# Switches.net
KiCad netlist of a schematic drawn in Altium Designer
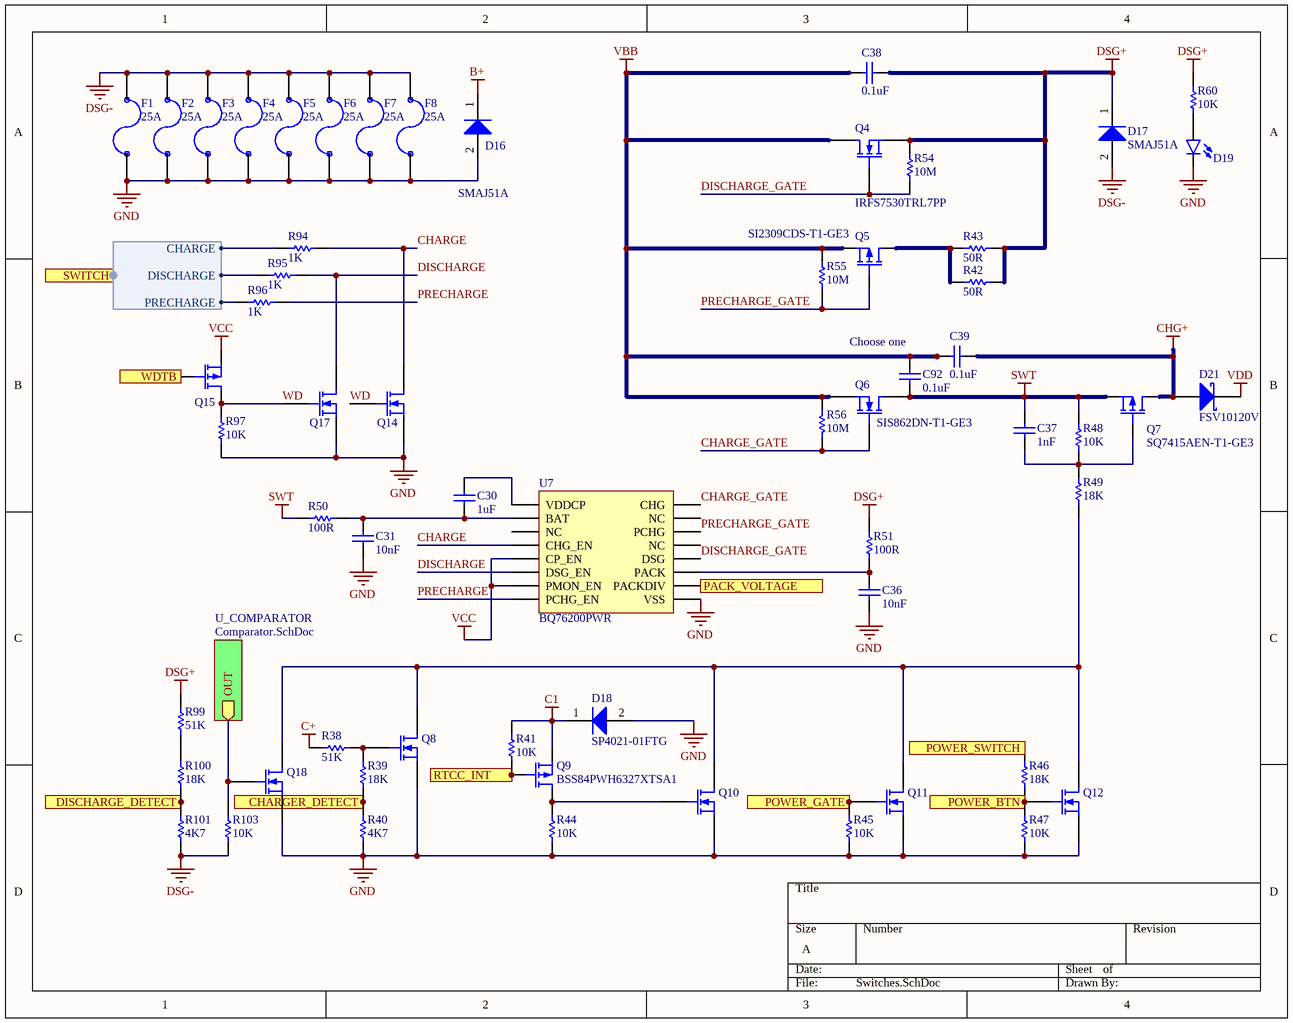
[diagram p0: Switches.SchDoc]

(export (version "E")
  (design (tool "Eeschema 10.0.6"))
  (components
    (comp (ref "C30")
      (value "1uF")
      (footprint "C0603[1608X92]")
      (description "1uF 50V 10% 0603 (1608 Metric)")
      (fields (field (name "TOLERANCE") "10%") (field (name "PARTNUMBER") "GRM188R61H105KAALD"))
      (libsource (lib "Capacitors") (part "CAP_1uF_50V_0603_10%"))
    )
    (comp (ref "C31")
      (value "10nF")
      (footprint "C0603[1608X92]")
      (description "10nF 100V 10% 0603 (1608 Metric)")
      (fields (field (name "TOLERANCE") "10%") (field (name "PARTNUMBER") "GRM188R72A103KA01D"))
      (libsource (lib "Capacitors") (part "CAP_10nF_100V_0603_10%"))
    )
    (comp (ref "C36")
      (value "10nF")
      (footprint "C0603[1608X92]")
      (description "10nF 100V 10% 0603 (1608 Metric)")
      (fields (field (name "TOLERANCE") "10%") (field (name "PARTNUMBER") "GRM188R72A103KA01D"))
      (libsource (lib "Capacitors") (part "CAP_10nF_100V_0603_10%"))
    )
    (comp (ref "C37")
      (value "1nF")
      (footprint "C0603[1608X92]")
      (description "1nF 50V 5% 0603 (1608 Metric)")
      (fields (field (name "PARTNUMBER") "GRM1885C1H102JA01D") (field (name "MANUFACTURER") "Murata"))
      (libsource (lib "Capacitors") (part "CAP_1nF_50V_0603_5%"))
    )
    (comp (ref "C38")
      (value "0.1uF")
      (footprint "C0603[1608X92]")
      (description "0.1uF 100V 10% 0603 (1608 Metric)")
      (fields (field (name "PARTNUMBER") "GRM188R72A104KA35D") (field (name "MANUFACTURER") "Murata"))
      (libsource (lib "Capacitors") (part "CAP_0.1uF_100V_0603_10%"))
    )
    (comp (ref "C39")
      (value "0.1uF")
      (footprint "C0603[1608X92]")
      (description "0.1uF 100V 10% 0603 (1608 Metric)")
      (fields (field (name "PARTNUMBER") "GRM188R72A104KA35D") (field (name "MANUFACTURER") "Murata"))
      (libsource (lib "Capacitors") (part "CAP_0.1uF_100V_0603_10%"))
    )
    (comp (ref "C92")
      (value "0.1uF")
      (footprint "C0603[1608X92]")
      (description "0.1uF 100V 10% 0603 (1608 Metric)")
      (fields (field (name "PARTNUMBER") "GRM188R72A104KA35D") (field (name "MANUFACTURER") "Murata"))
      (libsource (lib "Capacitors") (part "CAP_0.1uF_100V_0603_10%"))
    )
    (comp (ref "D16")
      (value "SMAJ51A")
      (footprint "DO-214AC")
      (fields (field (name "PARTNUMBER") "SMAJ51A-E3/61") (field (name "MANUFACTURER") "Vishay"))
      (libsource (lib "Diodes") (part "SMAJ51A-E3/61"))
    )
    (comp (ref "D17")
      (value "SMAJ51A")
      (footprint "DO-214AC")
      (fields (field (name "PARTNUMBER") "SMAJ51A-E3/61") (field (name "MANUFACTURER") "Vishay"))
      (libsource (lib "Diodes") (part "SMAJ51A-E3/61"))
    )
    (comp (ref "D18")
      (value "SP4021-01FTG")
      (footprint "SOD-323")
      (fields (field (name "MANUFACTURER") "Littelfuse"))
      (libsource (lib "Diodes") (part "SP4021-01FTG"))
    )
    (comp (ref "D19")
      (value "LED_0603_GREEN_5mA")
      (footprint "LED0603")
      (fields (field (name "PARTNUMBER") "LTST-C193TGKT-5A") (field (name "MANUFACTURER") "Lite-On Inc."))
      (libsource (lib "LEDs") (part "LED_0603_GREEN_5mA"))
    )
    (comp (ref "D21")
      (value "FSV10120V")
      (footprint "TO-277")
      (description "Schottky Diodes & Rectifiers 10 Amp 120V Schottky Rectifier")
      (fields (field (name "MANUFACTURER") "Fairchild Semiconductor"))
      (libsource (lib "Diodes") (part "FSV10120V"))
    )
    (comp (ref "F1")
      (value "FUSE 1206")
      (footprint "1206_FUSE")
      (description "Surface Mount Fuses UST 1206 FUSE 25A F")
      (fields
        (field (name "PARTNUMBER") "3413.0332.22")
        (field (name "MANUFACTURER") "Schurter")
        (field (name "CURRENT") "25A")
      )
      (libsource (lib "Components") (part "FUSE 1206"))
    )
    (comp (ref "F2")
      (value "FUSE 1206")
      (footprint "1206_FUSE")
      (description "Surface Mount Fuses UST 1206 FUSE 25A F")
      (fields
        (field (name "PARTNUMBER") "3413.0332.22")
        (field (name "MANUFACTURER") "Schurter")
        (field (name "CURRENT") "25A")
      )
      (libsource (lib "Components") (part "FUSE 1206"))
    )
    (comp (ref "F3")
      (value "FUSE 1206")
      (footprint "1206_FUSE")
      (description "Surface Mount Fuses UST 1206 FUSE 25A F")
      (fields
        (field (name "PARTNUMBER") "3413.0332.22")
        (field (name "MANUFACTURER") "Schurter")
        (field (name "CURRENT") "25A")
      )
      (libsource (lib "Components") (part "FUSE 1206"))
    )
    (comp (ref "F4")
      (value "FUSE 1206")
      (footprint "1206_FUSE")
      (description "Surface Mount Fuses UST 1206 FUSE 25A F")
      (fields
        (field (name "PARTNUMBER") "3413.0332.22")
        (field (name "MANUFACTURER") "Schurter")
        (field (name "CURRENT") "25A")
      )
      (libsource (lib "Components") (part "FUSE 1206"))
    )
    (comp (ref "F5")
      (value "FUSE 1206")
      (footprint "1206_FUSE")
      (description "Surface Mount Fuses UST 1206 FUSE 25A F")
      (fields
        (field (name "PARTNUMBER") "3413.0332.22")
        (field (name "MANUFACTURER") "Schurter")
        (field (name "CURRENT") "25A")
      )
      (libsource (lib "Components") (part "FUSE 1206"))
    )
    (comp (ref "F6")
      (value "FUSE 1206")
      (footprint "1206_FUSE")
      (description "Surface Mount Fuses UST 1206 FUSE 25A F")
      (fields
        (field (name "PARTNUMBER") "3413.0332.22")
        (field (name "MANUFACTURER") "Schurter")
        (field (name "CURRENT") "25A")
      )
      (libsource (lib "Components") (part "FUSE 1206"))
    )
    (comp (ref "F7")
      (value "FUSE 1206")
      (footprint "1206_FUSE")
      (description "Surface Mount Fuses UST 1206 FUSE 25A F")
      (fields
        (field (name "PARTNUMBER") "3413.0332.22")
        (field (name "MANUFACTURER") "Schurter")
        (field (name "CURRENT") "25A")
      )
      (libsource (lib "Components") (part "FUSE 1206"))
    )
    (comp (ref "F8")
      (value "FUSE 1206")
      (footprint "1206_FUSE")
      (description "Surface Mount Fuses UST 1206 FUSE 25A F")
      (fields
        (field (name "PARTNUMBER") "3413.0332.22")
        (field (name "MANUFACTURER") "Schurter")
        (field (name "CURRENT") "25A")
      )
      (libsource (lib "Components") (part "FUSE 1206"))
    )
    (comp (ref "Q4")
      (value "IRFS7530TRL7PP")
      (footprint "D2PAK-7  w/Heatsink")
      (description "N-Channel MOSFET")
      (fields (field (name "MANUFACTURER") "Infineon") (field (name "PUBLISHER") "Altium Limited"))
      (libsource (lib "MOSFETs") (part "IRFS7530TRL7PP"))
    )
    (comp (ref "Q5")
      (value "SI2309CDS-T1-GE3")
      (footprint "SOT23-3")
      (description "P-Channel MOSFET")
      (fields (field (name "MANUFACTURER") "Vishay"))
      (libsource (lib "MOSFETs") (part "SI2309CDS-T1-GE3"))
    )
    (comp (ref "Q6")
      (value "SIS862DN-T1-GE3")
      (footprint "PowerPak-1212-8")
      (description "N-Channel MOSFET")
      (fields (field (name "MANUFACTURER") "Vishay"))
      (libsource (lib "MOSFETs") (part "SIS862DN-T1-GE3"))
    )
    (comp (ref "Q7")
      (value "SQ7415AEN-T1-GE3")
      (footprint "PowerPak-1212-8")
      (description "P-Channel MOSFET")
      (fields (field (name "MANUFACTURER") "Vishay"))
      (libsource (lib "MOSFETs") (part "SQ7415AEN-T1-GE3"))
    )
    (comp (ref "Q8")
      (value "BSS123WQ-7-F")
      (footprint "SOT323-3")
      (description "N-Channel MOSFET")
      (fields (field (name "MANUFACTURER") "Diodes Incorporated"))
      (libsource (lib "MOSFETs") (part "BSS123WQ-7-F"))
    )
    (comp (ref "Q9")
      (value "BSS84PWH6327XTSA1")
      (footprint "SOT323-3")
      (description "P-Channel MOSFET")
      (fields (field (name "MANUFACTURER") "Infineon"))
      (libsource (lib "MOSFETs") (part "BSS84PW H6327"))
    )
    (comp (ref "Q10")
      (value "BSS123WQ-7-F")
      (footprint "SOT323-3")
      (description "N-Channel MOSFET")
      (fields (field (name "MANUFACTURER") "Diodes Incorporated"))
      (libsource (lib "MOSFETs") (part "BSS123WQ-7-F"))
    )
    (comp (ref "Q11")
      (value "BSS123WQ-7-F")
      (footprint "SOT323-3")
      (description "N-Channel MOSFET")
      (fields (field (name "MANUFACTURER") "Diodes Incorporated"))
      (libsource (lib "MOSFETs") (part "BSS123WQ-7-F"))
    )
    (comp (ref "Q12")
      (value "BSS123WQ-7-F")
      (footprint "SOT323-3")
      (description "N-Channel MOSFET")
      (fields (field (name "MANUFACTURER") "Diodes Incorporated"))
      (libsource (lib "MOSFETs") (part "BSS123WQ-7-F"))
    )
    (comp (ref "Q14")
      (value "BSS123WQ-7-F")
      (footprint "SOT323-3")
      (description "N-Channel MOSFET")
      (fields (field (name "MANUFACTURER") "Diodes Incorporated"))
      (libsource (lib "MOSFETs") (part "BSS123WQ-7-F"))
    )
    (comp (ref "Q15")
      (value "BSS84PWH6327XTSA1")
      (footprint "SOT323-3")
      (description "P-Channel MOSFET")
      (fields (field (name "MANUFACTURER") "Infineon"))
      (libsource (lib "MOSFETs") (part "BSS84PW H6327"))
    )
    (comp (ref "Q17")
      (value "BSS123WQ-7-F")
      (footprint "SOT323-3")
      (description "N-Channel MOSFET")
      (fields (field (name "MANUFACTURER") "Diodes Incorporated"))
      (libsource (lib "MOSFETs") (part "BSS123WQ-7-F"))
    )
    (comp (ref "Q18")
      (value "BSS123WQ-7-F")
      (footprint "SOT323-3")
      (description "N-Channel MOSFET")
      (fields (field (name "MANUFACTURER") "Diodes Incorporated"))
      (libsource (lib "MOSFETs") (part "BSS123WQ-7-F"))
    )
    (comp (ref "R38")
      (value "51K")
      (footprint "R0603[1608]")
      (description "51K 0.25W 1% 0603 (1005 Metric)")
      (fields (field (name "POWER") "0.25W") (field (name "TOLERANCE") "1%"))
      (libsource (lib "Resistors") (part "RES_51K_0603_1%"))
    )
    (comp (ref "R39")
      (value "18K")
      (footprint "R0603[1608]")
      (description "18K 0.25W 1% 0603 (1005 Metric)")
      (fields (field (name "TOLERANCE") "1%") (field (name "POWER") "0.25W"))
      (libsource (lib "Resistors") (part "RES_18K_0603_1%"))
    )
    (comp (ref "R40")
      (value "4K7")
      (footprint "R0603[1608]")
      (description "4K7 0.25W 1% 0603 (1005 Metric)")
      (fields (field (name "TOLERANCE") "1%") (field (name "POWER") "0.25W"))
      (libsource (lib "Resistors") (part "RES_4K7_0603_1%"))
    )
    (comp (ref "R41")
      (value "10K")
      (footprint "R0603[1608]")
      (description "10K 0.25W 1% 0603 (1005 Metric)")
      (fields (field (name "MANUFACTURER") "Vishay / Dale") (field (name "PARTNUMBER") "CRCW060310K0FKEAHP"))
      (libsource (lib "Resistors") (part "RES_10K_0603_1%"))
    )
    (comp (ref "R42")
      (value "50R")
      (footprint "R1206[3216]")
      (description "50R 2.4W 2% 1206 (3216 Metric)")
      (fields (field (name "TOLERANCE") "2%") (field (name "POWER") "2.4W"))
      (libsource (lib "Resistors") (part "RES_50R_1206_2%"))
    )
    (comp (ref "R43")
      (value "50R")
      (footprint "R1206[3216]")
      (description "50R 2.4W 2% 1206 (3216 Metric)")
      (fields (field (name "TOLERANCE") "2%") (field (name "POWER") "2.4W"))
      (libsource (lib "Resistors") (part "RES_50R_1206_2%"))
    )
    (comp (ref "R44")
      (value "10K")
      (footprint "R0603[1608]")
      (description "10K 0.25W 1% 0603 (1005 Metric)")
      (fields (field (name "MANUFACTURER") "Vishay / Dale") (field (name "PARTNUMBER") "CRCW060310K0FKEAHP"))
      (libsource (lib "Resistors") (part "RES_10K_0603_1%"))
    )
    (comp (ref "R45")
      (value "10K")
      (footprint "R0603[1608]")
      (description "10K 0.25W 1% 0603 (1005 Metric)")
      (fields (field (name "MANUFACTURER") "Vishay / Dale") (field (name "PARTNUMBER") "CRCW060310K0FKEAHP"))
      (libsource (lib "Resistors") (part "RES_10K_0603_1%"))
    )
    (comp (ref "R46")
      (value "18K")
      (footprint "R0603[1608]")
      (description "18K 0.25W 1% 0603 (1005 Metric)")
      (fields (field (name "TOLERANCE") "1%") (field (name "POWER") "0.25W"))
      (libsource (lib "Resistors") (part "RES_18K_0603_1%"))
    )
    (comp (ref "R47")
      (value "10K")
      (footprint "R0603[1608]")
      (description "10K 0.25W 1% 0603 (1005 Metric)")
      (fields (field (name "POWER") "0.25W") (field (name "TOLERANCE") "1%"))
      (libsource (lib "Resistors") (part "RES_10K_0603_1%"))
    )
    (comp (ref "R48")
      (value "10K")
      (footprint "R0603[1608]")
      (description "10K 0.25W 1% 0603 (1005 Metric)")
      (fields (field (name "TOLERANCE") "1%") (field (name "POWER") "0.25W"))
      (libsource (lib "Resistors") (part "RES_10K_0603_1%"))
    )
    (comp (ref "R49")
      (value "18K")
      (footprint "R0603[1608]")
      (description "18K 0.25W 1% 0603 (1005 Metric)")
      (fields (field (name "POWER") "0.25W") (field (name "TOLERANCE") "1%"))
      (libsource (lib "Resistors") (part "RES_18K_0603_1%"))
    )
    (comp (ref "R50")
      (value "100R")
      (footprint "R0603[1608]")
      (description "100R 0.25W 1% 0603 (1005 Metric)")
      (fields (field (name "POWER") "0.25W") (field (name "TOLERANCE") "1%"))
      (libsource (lib "Resistors") (part "RES_100R_0603_1%"))
    )
    (comp (ref "R51")
      (value "100R")
      (footprint "R0603[1608]")
      (description "100R 0.25W 1% 0603 (1005 Metric)")
      (fields (field (name "POWER") "0.25W") (field (name "TOLERANCE") "1%"))
      (libsource (lib "Resistors") (part "RES_100R_0603_1%"))
    )
    (comp (ref "R54")
      (value "10M")
      (footprint "R0603[1608]")
      (description "10M 0.25W 1% 0603 (1005 Metric)")
      (fields (field (name "MANUFACTURER") "Vishay / Dale") (field (name "PARTNUMBER") "RCS060310M0FKEA"))
      (libsource (lib "Resistors") (part "RES_10M_0603_1%"))
    )
    (comp (ref "R55")
      (value "10M")
      (footprint "R0603[1608]")
      (description "10M 0.25W 1% 0603 (1005 Metric)")
      (fields (field (name "MANUFACTURER") "Vishay / Dale") (field (name "PARTNUMBER") "RCS060310M0FKEA"))
      (libsource (lib "Resistors") (part "RES_10M_0603_1%"))
    )
    (comp (ref "R56")
      (value "10M")
      (footprint "R0603[1608]")
      (description "10M 0.25W 1% 0603 (1005 Metric)")
      (fields (field (name "MANUFACTURER") "Vishay / Dale") (field (name "PARTNUMBER") "RCS060310M0FKEA"))
      (libsource (lib "Resistors") (part "RES_10M_0603_1%"))
    )
    (comp (ref "R60")
      (value "10K")
      (footprint "R0603[1608]")
      (description "10K 0.25W 1% 0603 (1005 Metric)")
      (fields (field (name "TOLERANCE") "1%") (field (name "POWER") "0.25W"))
      (libsource (lib "Resistors") (part "RES_10K_0603_1%"))
    )
    (comp (ref "R94")
      (value "1K")
      (footprint "R0603[1608]")
      (description "1K 0.25W 1% 0603 (1005 Metric)")
      (fields (field (name "MANUFACTURER") "Vishay / Dale") (field (name "PARTNUMBER") "CRCW06031K00FKEAHP"))
      (libsource (lib "Resistors") (part "RES_1K_0603_1%"))
    )
    (comp (ref "R95")
      (value "1K")
      (footprint "R0603[1608]")
      (description "1K 0.25W 1% 0603 (1005 Metric)")
      (fields (field (name "MANUFACTURER") "Vishay / Dale") (field (name "PARTNUMBER") "CRCW06031K00FKEAHP"))
      (libsource (lib "Resistors") (part "RES_1K_0603_1%"))
    )
    (comp (ref "R96")
      (value "1K")
      (footprint "R0603[1608]")
      (description "1K 0.25W 1% 0603 (1005 Metric)")
      (fields (field (name "MANUFACTURER") "Vishay / Dale") (field (name "PARTNUMBER") "CRCW06031K00FKEAHP"))
      (libsource (lib "Resistors") (part "RES_1K_0603_1%"))
    )
    (comp (ref "R97")
      (value "10K")
      (footprint "R0603[1608]")
      (description "10K 0.25W 1% 0603 (1005 Metric)")
      (fields (field (name "MANUFACTURER") "Vishay / Dale") (field (name "PARTNUMBER") "CRCW060310K0FKEAHP"))
      (libsource (lib "Resistors") (part "RES_10K_0603_1%"))
    )
    (comp (ref "R99")
      (value "51K")
      (footprint "R0603[1608]")
      (description "51K 0.25W 1% 0603 (1005 Metric)")
      (fields (field (name "POWER") "0.25W") (field (name "TOLERANCE") "1%"))
      (libsource (lib "Resistors") (part "RES_51K_0603_1%"))
    )
    (comp (ref "R100")
      (value "18K")
      (footprint "R0603[1608]")
      (description "18K 0.25W 1% 0603 (1005 Metric)")
      (fields (field (name "TOLERANCE") "1%") (field (name "POWER") "0.25W"))
      (libsource (lib "Resistors") (part "RES_18K_0603_1%"))
    )
    (comp (ref "R101")
      (value "4K7")
      (footprint "R0603[1608]")
      (description "4K7 0.25W 1% 0603 (1005 Metric)")
      (fields (field (name "TOLERANCE") "1%") (field (name "POWER") "0.25W"))
      (libsource (lib "Resistors") (part "RES_4K7_0603_1%"))
    )
    (comp (ref "R103")
      (value "10K")
      (footprint "R0603[1608]")
      (description "10K 0.25W 1% 0603 (1005 Metric)")
      (fields (field (name "MANUFACTURER") "Vishay / Dale") (field (name "PARTNUMBER") "CRCW060310K0FKEAHP"))
      (libsource (lib "Resistors") (part "RES_10K_0603_1%"))
    )
    (comp (ref "U7")
      (value "BQ76200PWR")
      (footprint "TSSOP-16")
      (description "Battery Management Fast high side NCH drive")
      (fields (field (name "MANUFACTURER") "Texas Instruments"))
      (libsource (lib "ICs") (part "BQ76200PWR"))
    )
  )
  (nets
    (net (code "2") (name "/CHARGE") (class "Default")
      (node (ref "Q14") (pin "3") (pinfunction "D_3") (pintype "passive"))
      (node (ref "R94") (pin "1") (pinfunction "1_1") (pintype "passive"))
      (node (ref "U7") (pin "4") (pinfunction "CHG_EN_4") (pintype "passive"))
    )
    (net (code "3") (name "/CHARGER_DETECT") (class "Default")
      (node (ref "R39") (pin "1") (pinfunction "1_1") (pintype "passive"))
      (node (ref "R40") (pin "2") (pinfunction "2_2") (pintype "passive"))
    )
    (net (code "4") (name "/CHARGE_GATE") (class "Default")
      (node (ref "Q6") (pin "2") (pinfunction "G_2") (pintype "passive"))
      (node (ref "R56") (pin "1") (pinfunction "1_1") (pintype "passive"))
      (node (ref "U7") (pin "16") (pinfunction "CHG_16") (pintype "passive"))
    )
    (net (code "5") (name "/DISCHARGE") (class "Default")
      (node (ref "Q17") (pin "3") (pinfunction "D_3") (pintype "passive"))
      (node (ref "R95") (pin "1") (pinfunction "1_1") (pintype "passive"))
      (node (ref "U7") (pin "6") (pinfunction "DSG_EN_6") (pintype "passive"))
    )
    (net (code "6") (name "/DISCHARGE_DETECT") (class "Default")
      (node (ref "R100") (pin "1") (pinfunction "1_1") (pintype "passive"))
      (node (ref "R101") (pin "2") (pinfunction "2_2") (pintype "passive"))
    )
    (net (code "7") (name "/DISCHARGE_GATE") (class "Default")
      (node (ref "Q4") (pin "1") (pinfunction "G_1") (pintype "passive"))
      (node (ref "R54") (pin "1") (pinfunction "1_1") (pintype "passive"))
      (node (ref "U7") (pin "12") (pinfunction "DSG_12") (pintype "passive"))
    )
    (net (code "8") (name "/OUT") (class "Default")
      (node (ref "Q18") (pin "1") (pinfunction "G_1") (pintype "passive"))
      (node (ref "R103") (pin "2") (pinfunction "2_2") (pintype "passive"))
    )
    (net (code "9") (name "/PACK_VOLTAGE") (class "Default")
      (node (ref "U7") (pin "10") (pinfunction "PACKDIV_10") (pintype "passive"))
    )
    (net (code "10") (name "/POWER_BTN") (class "Default")
      (node (ref "Q12") (pin "1") (pinfunction "G_1") (pintype "passive"))
      (node (ref "R46") (pin "1") (pinfunction "1_1") (pintype "passive"))
      (node (ref "R47") (pin "2") (pinfunction "2_2") (pintype "passive"))
    )
    (net (code "11") (name "/POWER_GATE") (class "Default")
      (node (ref "Q11") (pin "1") (pinfunction "G_1") (pintype "passive"))
      (node (ref "R45") (pin "2") (pinfunction "2_2") (pintype "passive"))
    )
    (net (code "12") (name "/POWER_SWITCH") (class "Default")
      (node (ref "R46") (pin "2") (pinfunction "2_2") (pintype "passive"))
    )
    (net (code "13") (name "/PRECHARGE") (class "Default")
      (node (ref "R96") (pin "1") (pinfunction "1_1") (pintype "passive"))
      (node (ref "U7") (pin "8") (pinfunction "PCHG_EN_8") (pintype "passive"))
    )
    (net (code "14") (name "/PRECHARGE_GATE") (class "Default")
      (node (ref "Q5") (pin "1") (pinfunction "G_1") (pintype "passive"))
      (node (ref "R55") (pin "1") (pinfunction "1_1") (pintype "passive"))
      (node (ref "U7") (pin "14") (pinfunction "PCHG_14") (pintype "passive"))
    )
    (net (code "15") (name "/RTCC_INT") (class "Default")
      (node (ref "Q9") (pin "1") (pinfunction "G_1") (pintype "passive"))
      (node (ref "R41") (pin "2") (pinfunction "2_2") (pintype "passive"))
    )
    (net (code "16") (name "/WD") (class "Default")
      (node (ref "Q14") (pin "1") (pinfunction "G_1") (pintype "passive"))
      (node (ref "Q15") (pin "3") (pinfunction "D_3") (pintype "passive"))
      (node (ref "Q17") (pin "1") (pinfunction "G_1") (pintype "passive"))
      (node (ref "R97") (pin "2") (pinfunction "2_2") (pintype "passive"))
    )
    (net (code "17") (name "/WDTB") (class "Default")
      (node (ref "Q15") (pin "1") (pinfunction "G_1") (pintype "passive"))
    )
    (net (code "19") (name "B+") (class "Default")
      (node (ref "D16") (pin "1") (pinfunction "K_1") (pintype "passive"))
    )
    (net (code "20") (name "C+") (class "Default")
      (node (ref "R38") (pin "2") (pinfunction "2_2") (pintype "passive"))
    )
    (net (code "21") (name "C1") (class "Default")
      (node (ref "D18") (pin "1") (pinfunction "K_1") (pintype "passive"))
      (node (ref "Q9") (pin "2") (pinfunction "S_2") (pintype "passive"))
      (node (ref "R41") (pin "1") (pinfunction "1_1") (pintype "passive"))
    )
    (net (code "22") (name "CHG+") (class "Default")
      (node (ref "C39") (pin "2") (pinfunction "2_2") (pintype "passive"))
      (node (ref "D21") (pin "2") (pinfunction "A_2") (pintype "passive"))
      (node (ref "Q7") (pin "3") (pinfunction "D_3") (pintype "passive"))
    )
    (net (code "23") (name "DSG+") (class "Default")
      (node (ref "C38") (pin "2") (pinfunction "2_2") (pintype "passive"))
      (node (ref "D17") (pin "1") (pinfunction "K_1") (pintype "passive"))
      (node (ref "Q4") (pin "2") (pinfunction "S_2") (pintype "passive"))
      (node (ref "R42") (pin "2") (pinfunction "2_2") (pintype "passive"))
      (node (ref "R43") (pin "2") (pinfunction "2_2") (pintype "passive"))
      (node (ref "R51") (pin "2") (pinfunction "2_2") (pintype "passive"))
      (node (ref "R54") (pin "2") (pinfunction "2_2") (pintype "passive"))
      (node (ref "R60") (pin "2") (pinfunction "2_2") (pintype "passive"))
      (node (ref "R99") (pin "1") (pinfunction "1_1") (pintype "passive"))
    )
    (net (code "24") (name "DSG-") (class "Default")
      (node (ref "D17") (pin "2") (pinfunction "A_2") (pintype "passive"))
      (node (ref "F1") (pin "1") (pinfunction "1_1") (pintype "passive"))
      (node (ref "F2") (pin "1") (pinfunction "1_1") (pintype "passive"))
      (node (ref "F3") (pin "1") (pinfunction "1_1") (pintype "passive"))
      (node (ref "F4") (pin "1") (pinfunction "1_1") (pintype "passive"))
      (node (ref "F5") (pin "1") (pinfunction "1_1") (pintype "passive"))
      (node (ref "F6") (pin "1") (pinfunction "1_1") (pintype "passive"))
      (node (ref "F7") (pin "1") (pinfunction "1_1") (pintype "passive"))
      (node (ref "F8") (pin "1") (pinfunction "1_1") (pintype "passive"))
      (node (ref "R101") (pin "1") (pinfunction "1_1") (pintype "passive"))
      (node (ref "R103") (pin "1") (pinfunction "1_1") (pintype "passive"))
    )
    (net (code "25") (name "GND") (class "Default")
      (node (ref "C31") (pin "1") (pinfunction "1_1") (pintype "passive"))
      (node (ref "C36") (pin "1") (pinfunction "1_1") (pintype "passive"))
      (node (ref "D16") (pin "2") (pinfunction "A_2") (pintype "passive"))
      (node (ref "D18") (pin "2") (pinfunction "A_2") (pintype "passive"))
      (node (ref "D19") (pin "C") (pinfunction "C_C") (pintype "passive"))
      (node (ref "F1") (pin "2") (pinfunction "2_2") (pintype "passive"))
      (node (ref "F2") (pin "2") (pinfunction "2_2") (pintype "passive"))
      (node (ref "F3") (pin "2") (pinfunction "2_2") (pintype "passive"))
      (node (ref "F4") (pin "2") (pinfunction "2_2") (pintype "passive"))
      (node (ref "F5") (pin "2") (pinfunction "2_2") (pintype "passive"))
      (node (ref "F6") (pin "2") (pinfunction "2_2") (pintype "passive"))
      (node (ref "F7") (pin "2") (pinfunction "2_2") (pintype "passive"))
      (node (ref "F8") (pin "2") (pinfunction "2_2") (pintype "passive"))
      (node (ref "Q10") (pin "2") (pinfunction "S_2") (pintype "passive"))
      (node (ref "Q11") (pin "2") (pinfunction "S_2") (pintype "passive"))
      (node (ref "Q12") (pin "2") (pinfunction "S_2") (pintype "passive"))
      (node (ref "Q14") (pin "2") (pinfunction "S_2") (pintype "passive"))
      (node (ref "Q17") (pin "2") (pinfunction "S_2") (pintype "passive"))
      (node (ref "Q18") (pin "2") (pinfunction "S_2") (pintype "passive"))
      (node (ref "Q8") (pin "2") (pinfunction "S_2") (pintype "passive"))
      (node (ref "R40") (pin "1") (pinfunction "1_1") (pintype "passive"))
      (node (ref "R44") (pin "1") (pinfunction "1_1") (pintype "passive"))
      (node (ref "R45") (pin "1") (pinfunction "1_1") (pintype "passive"))
      (node (ref "R47") (pin "1") (pinfunction "1_1") (pintype "passive"))
      (node (ref "R97") (pin "1") (pinfunction "1_1") (pintype "passive"))
      (node (ref "U7") (pin "9") (pinfunction "VSS_9") (pintype "passive"))
    )
    (net (code "26") (name "Net-(D19-PadA)") (class "Default")
      (node (ref "D19") (pin "A") (pinfunction "A_A") (pintype "passive"))
      (node (ref "R60") (pin "1") (pinfunction "1_1") (pintype "passive"))
    )
    (net (code "27") (name "Net-(Q5-D)") (class "Default")
      (node (ref "Q5") (pin "2") (pinfunction "D_2") (pintype "passive"))
      (node (ref "R42") (pin "1") (pinfunction "1_1") (pintype "passive"))
      (node (ref "R43") (pin "1") (pinfunction "1_1") (pintype "passive"))
    )
    (net (code "28") (name "Net-(Q7-G)") (class "Default")
      (node (ref "C37") (pin "1") (pinfunction "1_1") (pintype "passive"))
      (node (ref "Q7") (pin "2") (pinfunction "G_2") (pintype "passive"))
      (node (ref "R48") (pin "1") (pinfunction "1_1") (pintype "passive"))
      (node (ref "R49") (pin "2") (pinfunction "2_2") (pintype "passive"))
    )
    (net (code "29") (name "Net-(Q8-G)") (class "Default")
      (node (ref "Q8") (pin "1") (pinfunction "G_1") (pintype "passive"))
      (node (ref "R38") (pin "1") (pinfunction "1_1") (pintype "passive"))
      (node (ref "R39") (pin "2") (pinfunction "2_2") (pintype "passive"))
    )
    (net (code "30") (name "Net-(Q10-D)") (class "Default")
      (node (ref "Q10") (pin "3") (pinfunction "D_3") (pintype "passive"))
      (node (ref "Q11") (pin "3") (pinfunction "D_3") (pintype "passive"))
      (node (ref "Q12") (pin "3") (pinfunction "D_3") (pintype "passive"))
      (node (ref "Q18") (pin "3") (pinfunction "D_3") (pintype "passive"))
      (node (ref "Q8") (pin "3") (pinfunction "D_3") (pintype "passive"))
      (node (ref "R49") (pin "1") (pinfunction "1_1") (pintype "passive"))
    )
    (net (code "31") (name "Net-(Q10-G)") (class "Default")
      (node (ref "Q10") (pin "1") (pinfunction "G_1") (pintype "passive"))
      (node (ref "Q9") (pin "3") (pinfunction "D_3") (pintype "passive"))
      (node (ref "R44") (pin "2") (pinfunction "2_2") (pintype "passive"))
    )
    (net (code "32") (name "Net-(R100-Pad2)") (class "Default")
      (node (ref "R100") (pin "2") (pinfunction "2_2") (pintype "passive"))
      (node (ref "R99") (pin "2") (pinfunction "2_2") (pintype "passive"))
    )
    (net (code "33") (name "Net-(U7-BAT)") (class "Default")
      (node (ref "C30") (pin "1") (pinfunction "1_1") (pintype "passive"))
      (node (ref "C31") (pin "2") (pinfunction "2_2") (pintype "passive"))
      (node (ref "R50") (pin "2") (pinfunction "2_2") (pintype "passive"))
      (node (ref "U7") (pin "2") (pinfunction "BAT_2") (pintype "passive"))
    )
    (net (code "34") (name "Net-(U7-PACK)") (class "Default")
      (node (ref "C36") (pin "2") (pinfunction "2_2") (pintype "passive"))
      (node (ref "R51") (pin "1") (pinfunction "1_1") (pintype "passive"))
      (node (ref "U7") (pin "11") (pinfunction "PACK_11") (pintype "passive"))
    )
    (net (code "35") (name "Net-(U7-VDDCP)") (class "Default")
      (node (ref "C30") (pin "2") (pinfunction "2_2") (pintype "passive"))
      (node (ref "U7") (pin "1") (pinfunction "VDDCP_1") (pintype "passive"))
    )
    (net (code "36") (name "SWT") (class "Default")
      (node (ref "C37") (pin "2") (pinfunction "2_2") (pintype "passive"))
      (node (ref "C92") (pin "1") (pinfunction "1_1") (pintype "passive"))
      (node (ref "Q6") (pin "3") (pinfunction "D_3") (pintype "passive"))
      (node (ref "Q7") (pin "1") (pinfunction "S_1") (pintype "passive"))
      (node (ref "R48") (pin "2") (pinfunction "2_2") (pintype "passive"))
      (node (ref "R50") (pin "1") (pinfunction "1_1") (pintype "passive"))
    )
    (net (code "37") (name "VBB") (class "Default")
      (node (ref "C38") (pin "1") (pinfunction "1_1") (pintype "passive"))
      (node (ref "C39") (pin "1") (pinfunction "1_1") (pintype "passive"))
      (node (ref "C92") (pin "2") (pinfunction "2_2") (pintype "passive"))
      (node (ref "Q4") (pin "3") (pinfunction "D_3") (pintype "passive"))
      (node (ref "Q5") (pin "3") (pinfunction "S_3") (pintype "passive"))
      (node (ref "Q6") (pin "1") (pinfunction "S_1") (pintype "passive"))
      (node (ref "R55") (pin "2") (pinfunction "2_2") (pintype "passive"))
      (node (ref "R56") (pin "2") (pinfunction "2_2") (pintype "passive"))
    )
    (net (code "38") (name "VCC") (class "Default")
      (node (ref "Q15") (pin "2") (pinfunction "S_2") (pintype "passive"))
      (node (ref "U7") (pin "5") (pinfunction "CP_EN_5") (pintype "passive"))
      (node (ref "U7") (pin "7") (pinfunction "PMON_EN_7") (pintype "passive"))
    )
    (net (code "39") (name "VDD") (class "Default")
      (node (ref "D21") (pin "1") (pinfunction "K_1") (pintype "passive"))
    )
    (net (code "40") (name "unconnected-(R94-Pad2)") (class "Default")
      (node (ref "R94") (pin "2") (pinfunction "2_2") (pintype "passive"))
    )
    (net (code "41") (name "unconnected-(R95-Pad2)") (class "Default")
      (node (ref "R95") (pin "2") (pinfunction "2_2") (pintype "passive"))
    )
    (net (code "42") (name "unconnected-(R96-Pad2)") (class "Default")
      (node (ref "R96") (pin "2") (pinfunction "2_2") (pintype "passive"))
    )
    (net (code "43") (name "unconnected-(U7-NC-Pad3)") (class "Default")
      (node (ref "U7") (pin "3") (pinfunction "NC_3") (pintype "passive"))
    )
    (net (code "44") (name "unconnected-(U7-NC-Pad13)") (class "Default")
      (node (ref "U7") (pin "13") (pinfunction "NC_13") (pintype "passive"))
    )
    (net (code "45") (name "unconnected-(U7-NC-Pad15)") (class "Default")
      (node (ref "U7") (pin "15") (pinfunction "NC_15") (pintype "passive"))
    )
  )
)
